# PCB_Schematic.net
KiCad netlist of a schematic drawn in EAGLE
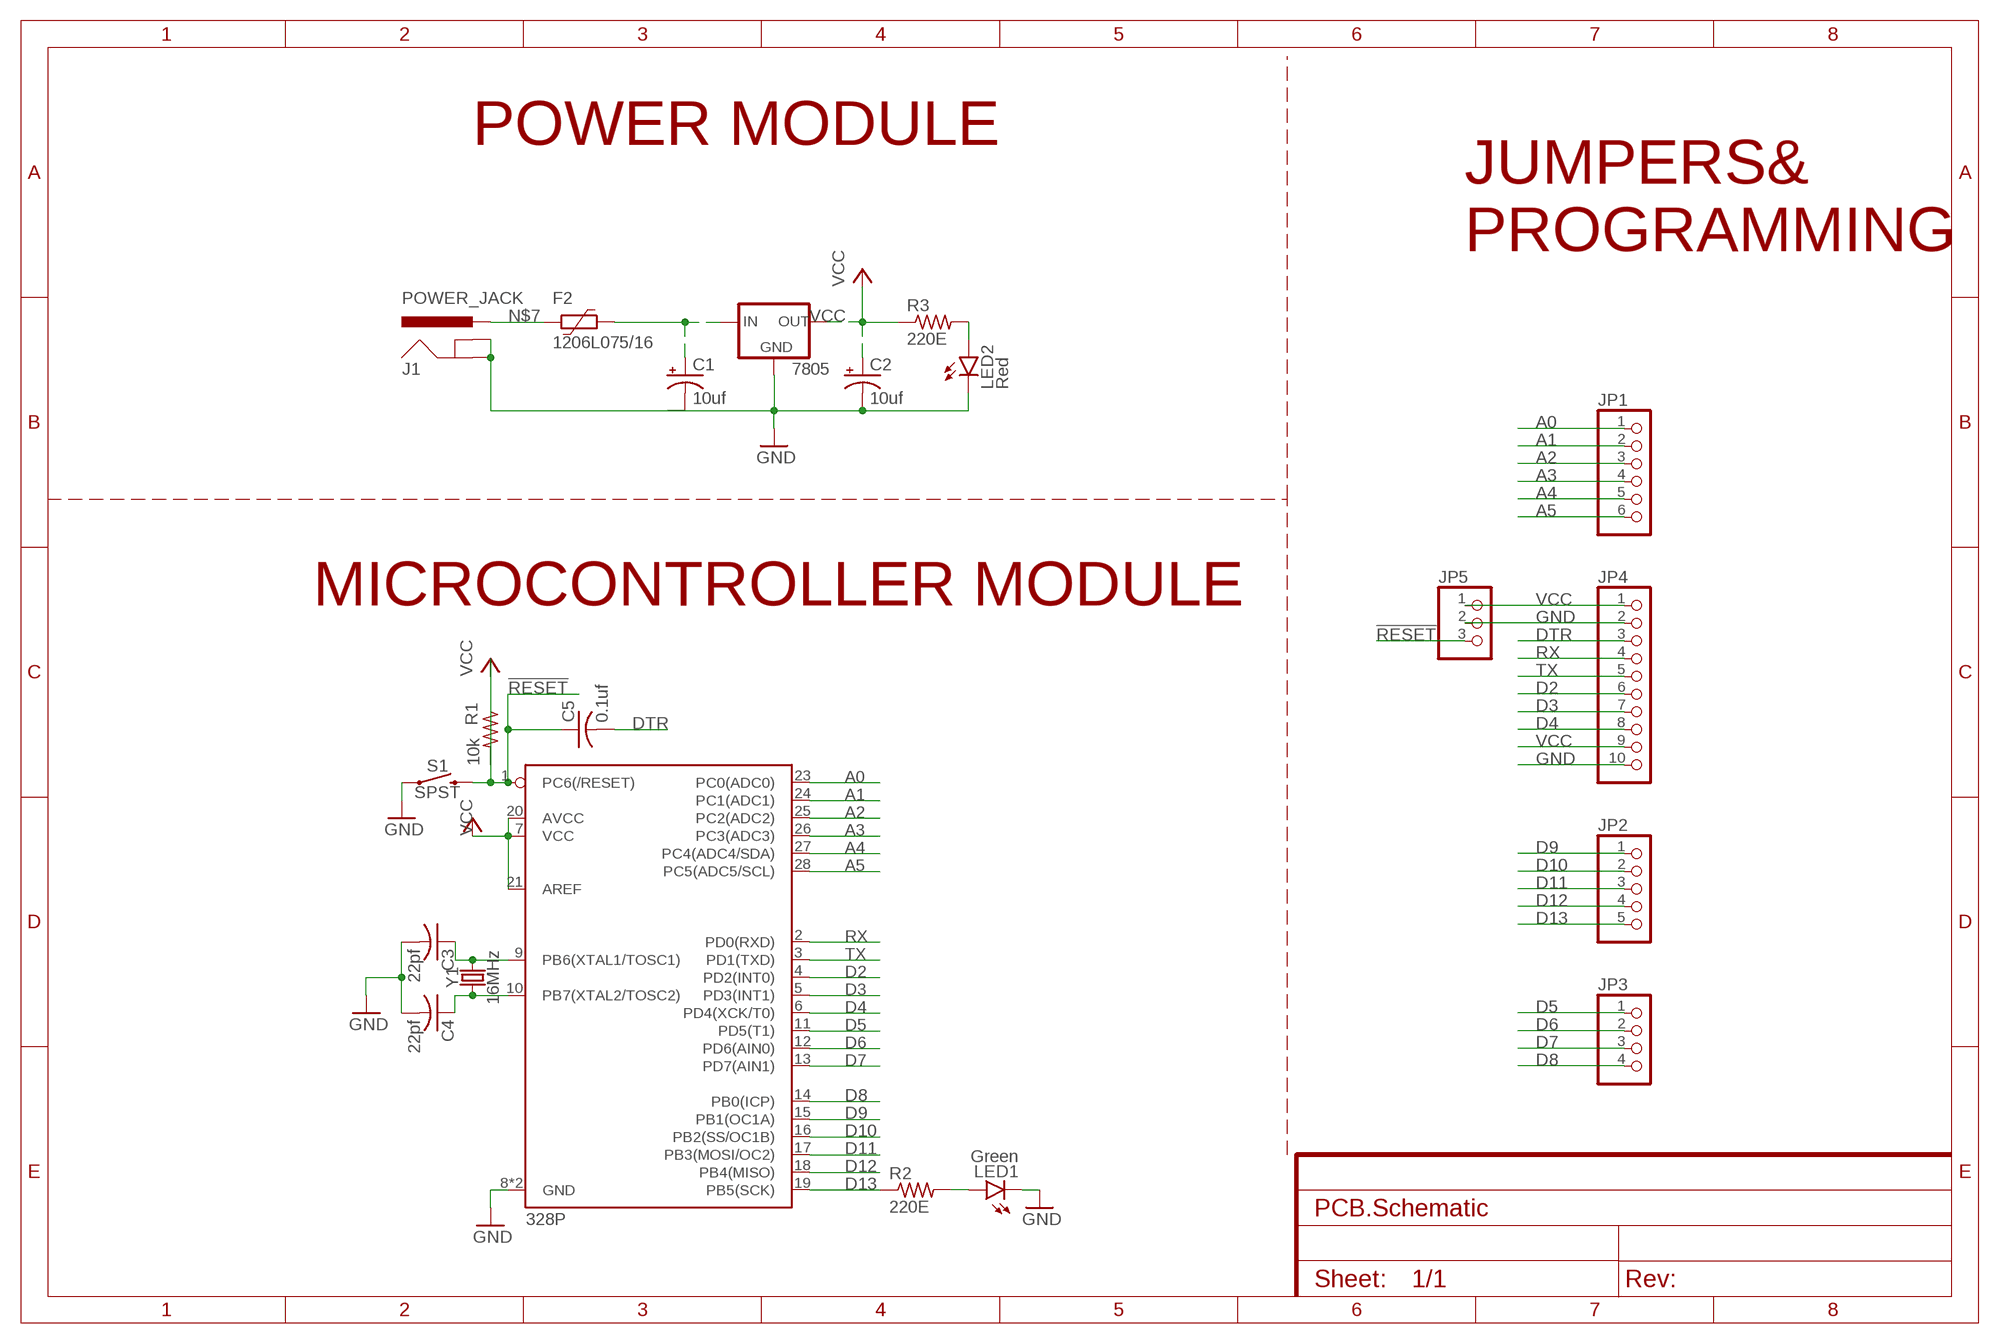
[diagram p0: schematic, sheet 1]

(export (version "E")
  (design (tool "Eeschema 10.0.6"))
  (components
    (comp (ref "C1")
      (value "10uf")
      (footprint "eagle-import:E2,5-6E")
      (libsource (lib "eagle-import") (part "CPOL-USE2,5-6E"))
    )
    (comp (ref "C2")
      (value "10uf")
      (footprint "eagle-import:E2,5-6E")
      (libsource (lib "eagle-import") (part "CPOL-USE2,5-6E"))
    )
    (comp (ref "C3")
      (value "22pf")
      (footprint "eagle-import:C025-024X044")
      (libsource (lib "eagle-import") (part "C-US025-024X044"))
    )
    (comp (ref "C4")
      (value "22pf")
      (footprint "eagle-import:C025-024X044")
      (libsource (lib "eagle-import") (part "C-US025-024X044"))
    )
    (comp (ref "C5")
      (value "0.1uf")
      (footprint "eagle-import:C025-024X044")
      (libsource (lib "eagle-import") (part "C-US025-024X044"))
    )
    (comp (ref "F2")
      (value "1206L075/16")
      (footprint "eagle-import:1206L")
      (fields (field (name "MF") "Littelfuse"))
      (libsource (lib "eagle-import") (part "?1206L075/16"))
    )
    (comp (ref "J1")
      (value "POWER_JACK")
      (footprint "eagle-import:POWER_JACK_PTH")
      (libsource (lib "eagle-import") (part "POWER_JACK"))
    )
    (comp (ref "JP1")
      (value "PINHD-1X6")
      (footprint "eagle-import:1X06")
      (libsource (lib "eagle-import") (part "PINHD-1X6"))
    )
    (comp (ref "JP2")
      (value "PINHD-1X5")
      (footprint "eagle-import:1X05")
      (libsource (lib "eagle-import") (part "PINHD-1X5"))
    )
    (comp (ref "JP3")
      (value "PINHD-1X4")
      (footprint "eagle-import:1X04")
      (libsource (lib "eagle-import") (part "PINHD-1X4"))
    )
    (comp (ref "JP4")
      (value "PINHD-1X10")
      (footprint "eagle-import:1X10")
      (libsource (lib "eagle-import") (part "PINHD-1X10"))
    )
    (comp (ref "JP5")
      (value "PINHD-1X3")
      (footprint "eagle-import:1X03")
      (libsource (lib "eagle-import") (part "PINHD-1X3"))
    )
    (comp (ref "LED1")
      (value "Green")
      (footprint "eagle-import:LED3MM")
      (libsource (lib "eagle-import") (part "LED3MM"))
    )
    (comp (ref "LED2")
      (value "Red")
      (footprint "eagle-import:LED3MM")
      (libsource (lib "eagle-import") (part "LED3MM"))
    )
    (comp (ref "R1")
      (value "10k")
      (footprint "eagle-import:0204_7")
      (libsource (lib "eagle-import") (part "R-US_0204/7"))
    )
    (comp (ref "R2")
      (value "220E")
      (footprint "eagle-import:0204_7")
      (libsource (lib "eagle-import") (part "R-US_0204/7"))
    )
    (comp (ref "R3")
      (value "220E")
      (footprint "eagle-import:0204_7")
      (libsource (lib "eagle-import") (part "R-US_0204/7"))
    )
    (comp (ref "S1")
      (value "SPST")
      (footprint "eagle-import:TACTILE_SWITCH_PTH_6.0MM")
      (libsource (lib "eagle-import") (part "MOMENTARY-SWITCH-SPST-PTH-6.0MM"))
    )
    (comp (ref "U1")
      (value "7805")
      (footprint "eagle-import:78XXS")
      (libsource (lib "eagle-import") (part "78XXS"))
    )
    (comp (ref "U2")
      (value "328P")
      (footprint "eagle-import:DIP28")
      (libsource (lib "eagle-import") (part "ATMEGA328P_PDIP"))
    )
    (comp (ref "Y1")
      (value "16MHz")
      (footprint "eagle-import:HC49US")
      (libsource (lib "eagle-import") (part "CRYSTAL-16MHZPTH-HC49US"))
    )
  )
  (nets
    (net (code "1") (name "/A0") (class "Default")
      (node (ref "JP1") (pin "1") (pinfunction "1_1") (pintype "passive"))
      (node (ref "U2") (pin "23") (pinfunction "PC0(ADC0)_23") (pintype "bidirectional"))
    )
    (net (code "2") (name "/A1") (class "Default")
      (node (ref "JP1") (pin "2") (pinfunction "2_2") (pintype "passive"))
      (node (ref "U2") (pin "24") (pinfunction "PC1(ADC1)_24") (pintype "bidirectional"))
    )
    (net (code "3") (name "/A2") (class "Default")
      (node (ref "JP1") (pin "3") (pinfunction "3_3") (pintype "passive"))
      (node (ref "U2") (pin "25") (pinfunction "PC2(ADC2)_25") (pintype "bidirectional"))
    )
    (net (code "4") (name "/A3") (class "Default")
      (node (ref "JP1") (pin "4") (pinfunction "4_4") (pintype "passive"))
      (node (ref "U2") (pin "26") (pinfunction "PC3(ADC3)_26") (pintype "bidirectional"))
    )
    (net (code "5") (name "/A4") (class "Default")
      (node (ref "JP1") (pin "5") (pinfunction "5_5") (pintype "passive"))
      (node (ref "U2") (pin "27") (pinfunction "PC4(ADC4/SDA)_27") (pintype "bidirectional"))
    )
    (net (code "6") (name "/A5") (class "Default")
      (node (ref "JP1") (pin "6") (pinfunction "6_6") (pintype "passive"))
      (node (ref "U2") (pin "28") (pinfunction "PC5(ADC5/SCL)_28") (pintype "bidirectional"))
    )
    (net (code "7") (name "/D2") (class "Default")
      (node (ref "JP4") (pin "6") (pinfunction "6_6") (pintype "passive"))
      (node (ref "U2") (pin "4") (pinfunction "PD2(INT0)_4") (pintype "bidirectional"))
    )
    (net (code "8") (name "/D3") (class "Default")
      (node (ref "JP4") (pin "7") (pinfunction "7_7") (pintype "passive"))
      (node (ref "U2") (pin "5") (pinfunction "PD3(INT1)_5") (pintype "bidirectional"))
    )
    (net (code "9") (name "/D4") (class "Default")
      (node (ref "JP4") (pin "8") (pinfunction "8_8") (pintype "passive"))
      (node (ref "U2") (pin "6") (pinfunction "PD4(XCK/T0)_6") (pintype "bidirectional"))
    )
    (net (code "10") (name "/D5") (class "Default")
      (node (ref "JP3") (pin "1") (pinfunction "1_1") (pintype "passive"))
      (node (ref "U2") (pin "11") (pinfunction "PD5(T1)_11") (pintype "bidirectional"))
    )
    (net (code "11") (name "/D6") (class "Default")
      (node (ref "JP3") (pin "2") (pinfunction "2_2") (pintype "passive"))
      (node (ref "U2") (pin "12") (pinfunction "PD6(AIN0)_12") (pintype "bidirectional"))
    )
    (net (code "12") (name "/D7") (class "Default")
      (node (ref "JP3") (pin "3") (pinfunction "3_3") (pintype "passive"))
      (node (ref "U2") (pin "13") (pinfunction "PD7(AIN1)_13") (pintype "bidirectional"))
    )
    (net (code "13") (name "/D8") (class "Default")
      (node (ref "JP3") (pin "4") (pinfunction "4_4") (pintype "passive"))
      (node (ref "U2") (pin "14") (pinfunction "PB0(ICP)_14") (pintype "bidirectional"))
    )
    (net (code "14") (name "/D9") (class "Default")
      (node (ref "JP2") (pin "1") (pinfunction "1_1") (pintype "passive"))
      (node (ref "U2") (pin "15") (pinfunction "PB1(OC1A)_15") (pintype "bidirectional"))
    )
    (net (code "15") (name "/D10") (class "Default")
      (node (ref "JP2") (pin "2") (pinfunction "2_2") (pintype "passive"))
      (node (ref "U2") (pin "16") (pinfunction "PB2(SS/OC1B)_16") (pintype "bidirectional"))
    )
    (net (code "16") (name "/D11") (class "Default")
      (node (ref "JP2") (pin "3") (pinfunction "3_3") (pintype "passive"))
      (node (ref "U2") (pin "17") (pinfunction "PB3(MOSI/OC2)_17") (pintype "bidirectional"))
    )
    (net (code "17") (name "/D12") (class "Default")
      (node (ref "JP2") (pin "4") (pinfunction "4_4") (pintype "passive"))
      (node (ref "U2") (pin "18") (pinfunction "PB4(MISO)_18") (pintype "bidirectional"))
    )
    (net (code "18") (name "/D13") (class "Default")
      (node (ref "JP2") (pin "5") (pinfunction "5_5") (pintype "passive"))
      (node (ref "R2") (pin "1") (pinfunction "1_1") (pintype "passive"))
      (node (ref "U2") (pin "19") (pinfunction "PB5(SCK)_19") (pintype "bidirectional"))
    )
    (net (code "19") (name "/DTR") (class "Default")
      (node (ref "C5") (pin "2") (pinfunction "2_2") (pintype "passive"))
      (node (ref "JP4") (pin "3") (pinfunction "3_3") (pintype "passive"))
    )
    (net (code "20") (name "/N$7") (class "Default")
      (node (ref "F2") (pin "2") (pinfunction "2_2") (pintype "passive"))
      (node (ref "J1") (pin "PWR") (pinfunction "PWR_PWR") (pintype "bidirectional"))
    )
    (net (code "21") (name "/RX") (class "Default")
      (node (ref "JP4") (pin "4") (pinfunction "4_4") (pintype "passive"))
      (node (ref "U2") (pin "2") (pinfunction "PD0(RXD)_2") (pintype "bidirectional"))
    )
    (net (code "22") (name "/TX") (class "Default")
      (node (ref "JP4") (pin "5") (pinfunction "5_5") (pintype "passive"))
      (node (ref "U2") (pin "3") (pinfunction "PD1(TXD)_3") (pintype "bidirectional"))
    )
    (net (code "23") (name "/~{RESET}") (class "Default")
      (node (ref "C5") (pin "1") (pinfunction "1_1") (pintype "passive"))
      (node (ref "JP5") (pin "3") (pinfunction "3_3") (pintype "passive"))
      (node (ref "R1") (pin "1") (pinfunction "1_1") (pintype "passive"))
      (node (ref "S1") (pin "3") (pinfunction "2_3") (pintype "passive"))
      (node (ref "U2") (pin "1") (pinfunction "PC6(/RESET)_1") (pintype "bidirectional"))
    )
    (net (code "24") (name "GND") (class "Default")
      (node (ref "C1") (pin "-") (pinfunction "-_-") (pintype "passive"))
      (node (ref "C2") (pin "-") (pinfunction "-_-") (pintype "passive"))
      (node (ref "C3") (pin "2") (pinfunction "2_2") (pintype "passive"))
      (node (ref "C4") (pin "2") (pinfunction "2_2") (pintype "passive"))
      (node (ref "J1") (pin "GND") (pinfunction "GND_GND") (pintype "bidirectional"))
      (node (ref "J1") (pin "GNDBREAK") (pinfunction "GNDBREAK_GNDBREAK") (pintype "bidirectional"))
      (node (ref "JP4") (pin "10") (pinfunction "10_10") (pintype "passive"))
      (node (ref "JP4") (pin "2") (pinfunction "2_2") (pintype "passive"))
      (node (ref "JP5") (pin "2") (pinfunction "2_2") (pintype "passive"))
      (node (ref "LED1") (pin "K") (pinfunction "C_K") (pintype "passive"))
      (node (ref "LED2") (pin "K") (pinfunction "C_K") (pintype "passive"))
      (node (ref "S1") (pin "1") (pinfunction "1_1") (pintype "passive"))
      (node (ref "U1") (pin "GND") (pinfunction "GND_GND") (pintype "input"))
      (node (ref "U2") (pin "22") (pinfunction "GND_22") (pintype "bidirectional"))
      (node (ref "U2") (pin "8") (pinfunction "GND_8") (pintype "bidirectional"))
    )
    (net (code "25") (name "Net-(C1-Pad+)") (class "Default")
      (node (ref "C1") (pin "+") (pinfunction "+_+") (pintype "passive"))
      (node (ref "F2") (pin "1") (pinfunction "1_1") (pintype "passive"))
      (node (ref "U1") (pin "IN") (pinfunction "IN_IN") (pintype "input"))
    )
    (net (code "26") (name "Net-(LED1-PadA)") (class "Default")
      (node (ref "LED1") (pin "A") (pinfunction "A_A") (pintype "passive"))
      (node (ref "R2") (pin "2") (pinfunction "2_2") (pintype "passive"))
    )
    (net (code "27") (name "Net-(LED2-PadA)") (class "Default")
      (node (ref "LED2") (pin "A") (pinfunction "A_A") (pintype "passive"))
      (node (ref "R3") (pin "2") (pinfunction "2_2") (pintype "passive"))
    )
    (net (code "28") (name "Net-(U2-PB6(XTAL1{slash}TOSC1))") (class "Default")
      (node (ref "C3") (pin "1") (pinfunction "1_1") (pintype "passive"))
      (node (ref "U2") (pin "9") (pinfunction "PB6(XTAL1/TOSC1)_9") (pintype "bidirectional"))
      (node (ref "Y1") (pin "2") (pinfunction "2_2") (pintype "passive"))
    )
    (net (code "29") (name "Net-(U2-PB7(XTAL2{slash}TOSC2))") (class "Default")
      (node (ref "C4") (pin "1") (pinfunction "1_1") (pintype "passive"))
      (node (ref "U2") (pin "10") (pinfunction "PB7(XTAL2/TOSC2)_10") (pintype "bidirectional"))
      (node (ref "Y1") (pin "1") (pinfunction "1_1") (pintype "passive"))
    )
    (net (code "30") (name "VCC") (class "Default")
      (node (ref "C2") (pin "+") (pinfunction "+_+") (pintype "passive"))
      (node (ref "JP4") (pin "1") (pinfunction "1_1") (pintype "passive"))
      (node (ref "JP4") (pin "9") (pinfunction "9_9") (pintype "passive"))
      (node (ref "JP5") (pin "1") (pinfunction "1_1") (pintype "passive"))
      (node (ref "R1") (pin "2") (pinfunction "2_2") (pintype "passive"))
      (node (ref "R3") (pin "1") (pinfunction "1_1") (pintype "passive"))
      (node (ref "U1") (pin "OUT") (pinfunction "OUT_OUT") (pintype "passive"))
      (node (ref "U2") (pin "20") (pinfunction "AVCC_20") (pintype "bidirectional"))
      (node (ref "U2") (pin "21") (pinfunction "AREF_21") (pintype "bidirectional"))
      (node (ref "U2") (pin "7") (pinfunction "VCC_7") (pintype "bidirectional"))
    )
  )
)
